# S65-Shield_v12.net
KiCad netlist of a schematic drawn in EAGLE
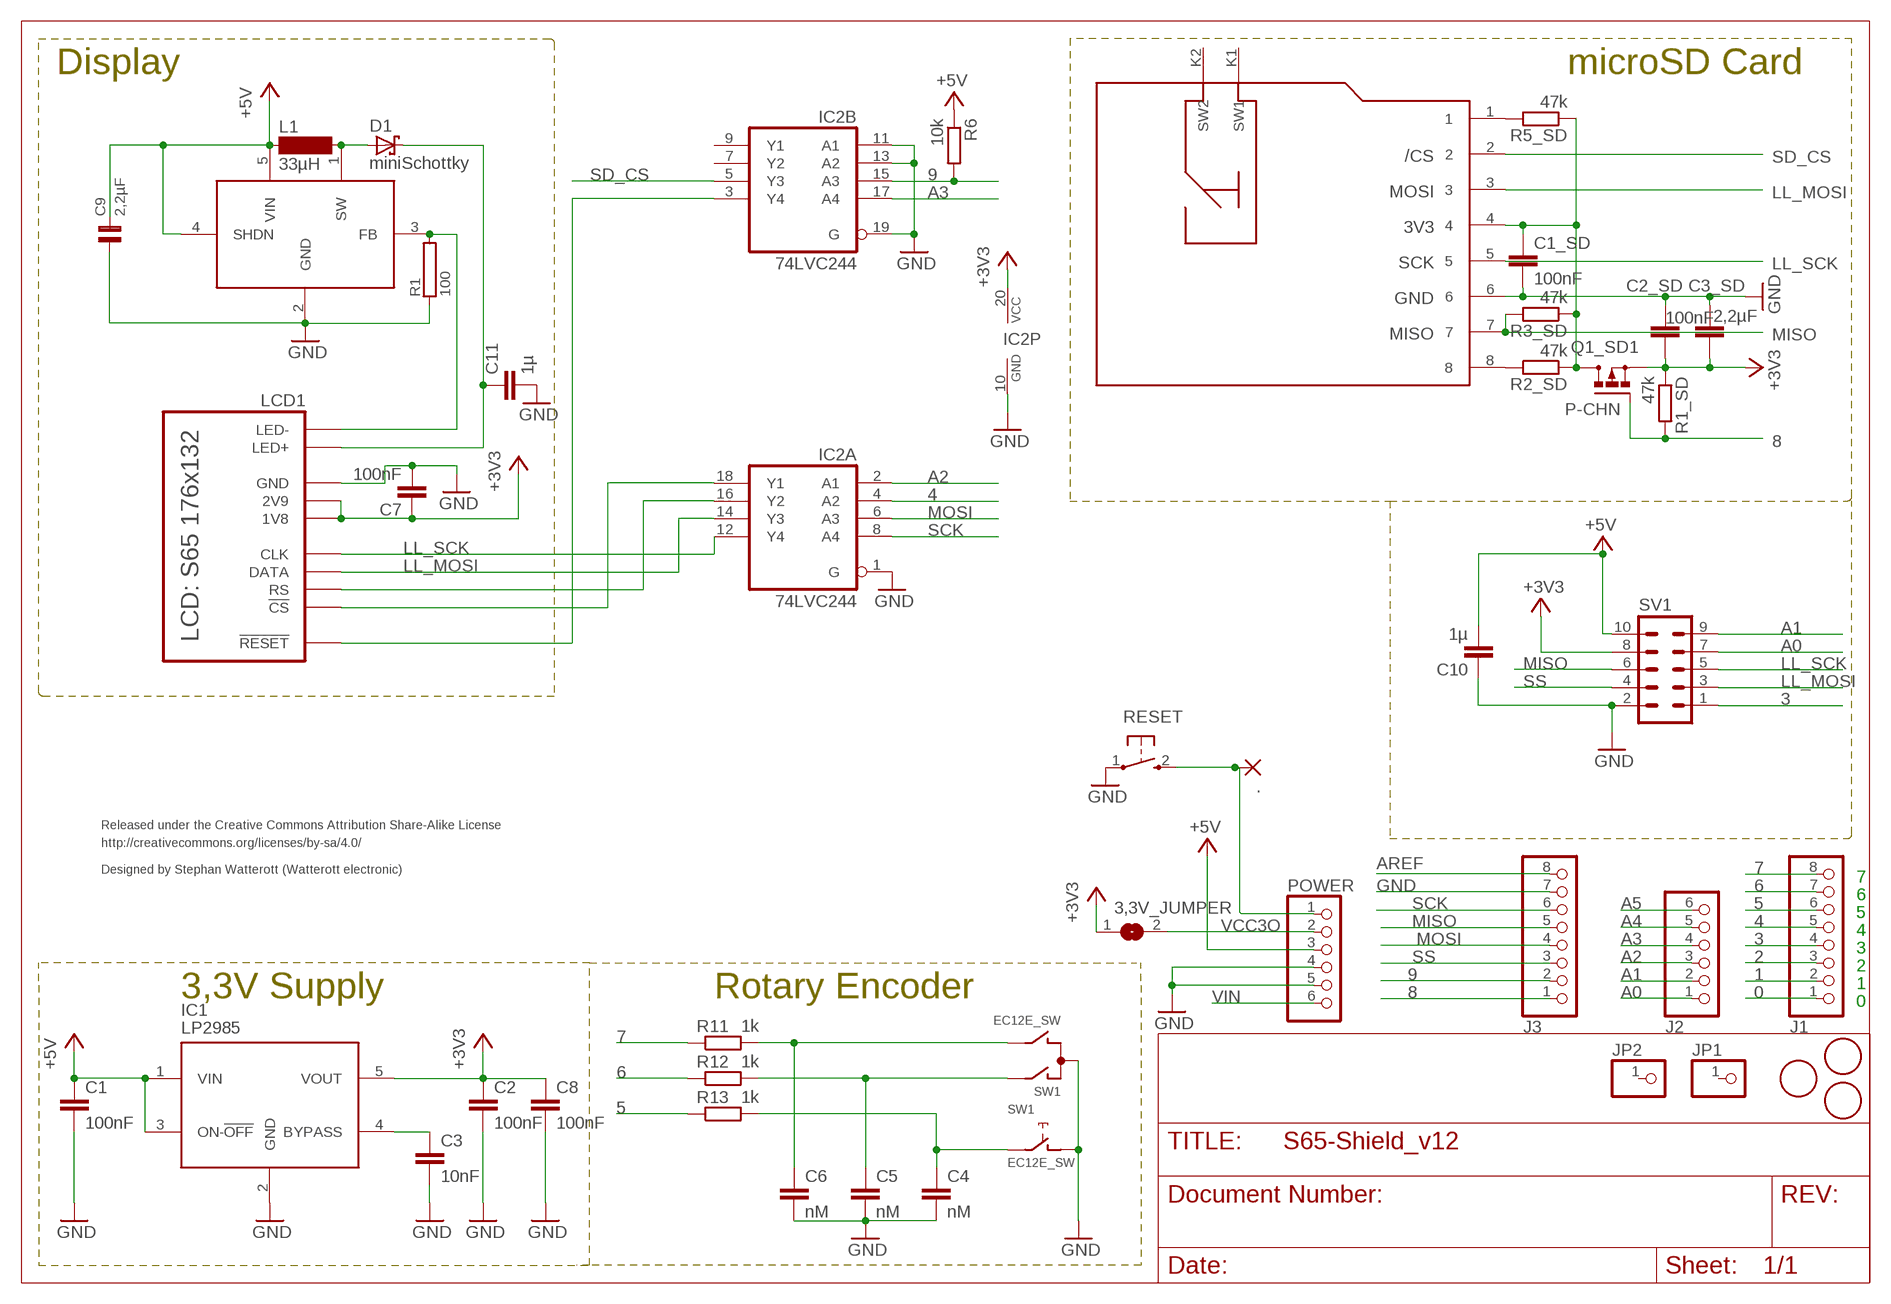
[diagram p0: schematic, sheet 1]

(export (version "E")
  (design (tool "Eeschema 10.0.6"))
  (components
    (comp (ref ".")
      (value "SMD2")
      (footprint "eagle-import:SMD1,27-2,54")
      (libsource (lib "eagle-import") (part "SMD2"))
    )
    (comp (ref "3,3V_JUMPER")
      (value "SJ")
      (footprint "eagle-import:SJ")
      (libsource (lib "eagle-import") (part "SJ"))
    )
    (comp (ref "C1")
      (value "100nF")
      (footprint "eagle-import:C0603")
      (libsource (lib "eagle-import") (part "resistor_C-EUC0603"))
    )
    (comp (ref "C1_SD")
      (value "100nF")
      (footprint "eagle-import:C0603")
      (libsource (lib "eagle-import") (part "C-EUC0603"))
    )
    (comp (ref "C2")
      (value "100nF")
      (footprint "eagle-import:C0603")
      (libsource (lib "eagle-import") (part "resistor_C-EUC0603"))
    )
    (comp (ref "C2_SD")
      (value "100nF")
      (footprint "eagle-import:C0603")
      (libsource (lib "eagle-import") (part "C-EUC0603"))
    )
    (comp (ref "C3")
      (value "10nF")
      (footprint "eagle-import:C0603")
      (libsource (lib "eagle-import") (part "resistor_C-EUC0603"))
    )
    (comp (ref "C3_SD")
      (value "2,2µF")
      (footprint "eagle-import:C0805")
      (libsource (lib "eagle-import") (part "C-EUC0805"))
    )
    (comp (ref "C4")
      (value "nM")
      (footprint "eagle-import:C0603")
      (libsource (lib "eagle-import") (part "resistor_C-EUC0603"))
    )
    (comp (ref "C5")
      (value "nM")
      (footprint "eagle-import:C0603")
      (libsource (lib "eagle-import") (part "resistor_C-EUC0603"))
    )
    (comp (ref "C6")
      (value "nM")
      (footprint "eagle-import:C0603")
      (libsource (lib "eagle-import") (part "resistor_C-EUC0603"))
    )
    (comp (ref "C7")
      (value "100nF")
      (footprint "eagle-import:C0603")
      (libsource (lib "eagle-import") (part "resistor_C-EUC0603"))
    )
    (comp (ref "C8")
      (value "100nF")
      (footprint "eagle-import:C0805")
      (libsource (lib "eagle-import") (part "resistor_C-EUC0805"))
    )
    (comp (ref "C9")
      (value "2,2µF")
      (footprint "eagle-import:0805")
      (libsource (lib "eagle-import") (part "CAP0805"))
    )
    (comp (ref "C10")
      (value "1µ")
      (footprint "eagle-import:C0603")
      (libsource (lib "eagle-import") (part "resistor_C-EUC0603"))
    )
    (comp (ref "C11")
      (value "1µ")
      (footprint "eagle-import:C0603")
      (libsource (lib "eagle-import") (part "resistor_C-EUC0603"))
    )
    (comp (ref "D1")
      (value "miniSchottky")
      (footprint "eagle-import:D0603")
      (libsource (lib "eagle-import") (part "DIODE0603"))
    )
    (comp (ref "IC1")
      (value "LP2985")
      (footprint "eagle-import:SOT23-5")
      (libsource (lib "eagle-import") (part "LP2985"))
    )
    (comp (ref "IC2")
      (value "74LVC244")
      (footprint "eagle-import:SO20W")
      (libsource (lib "eagle-import") (part "74244DWAC"))
    )
    (comp (ref "J1")
      (value "PINHD-1X8")
      (footprint "eagle-import:1X08")
      (libsource (lib "eagle-import") (part "PINHD-1X8"))
    )
    (comp (ref "J2")
      (value "PINHD-1X6")
      (footprint "eagle-import:1X06")
      (libsource (lib "eagle-import") (part "PINHD-1X6"))
    )
    (comp (ref "J3")
      (value "PINHD-1X8")
      (footprint "eagle-import:1X08")
      (libsource (lib "eagle-import") (part "PINHD-1X8"))
    )
    (comp (ref "JP1")
      (value "PINHD-1X1")
      (footprint "eagle-import:1X01")
      (libsource (lib "eagle-import") (part "PINHD-1X1"))
    )
    (comp (ref "JP2")
      (value "PINHD-1X1")
      (footprint "eagle-import:1X01")
      (libsource (lib "eagle-import") (part "PINHD-1X1"))
    )
    (comp (ref "L1")
      (value "33µH")
      (footprint "eagle-import:MS42")
      (libsource (lib "eagle-import") (part "MS42"))
    )
    (comp (ref "LCD1")
      (value "S65")
      (footprint "eagle-import:S65")
      (libsource (lib "eagle-import") (part "S65"))
    )
    (comp (ref "POWER")
      (value "PINHD-1X6")
      (footprint "eagle-import:1X06")
      (libsource (lib "eagle-import") (part "PINHD-1X6"))
    )
    (comp (ref "Q1_SD1")
      (value "P-CHN")
      (footprint "eagle-import:MICRO3")
      (libsource (lib "eagle-import") (part "IRLML6402"))
    )
    (comp (ref "R1")
      (value "100")
      (footprint "eagle-import:0603")
      (libsource (lib "eagle-import") (part "R0603"))
    )
    (comp (ref "R1_SD")
      (value "47k")
      (footprint "eagle-import:R0603")
      (libsource (lib "eagle-import") (part "R-EU_R0603"))
    )
    (comp (ref "R2_SD")
      (value "47k")
      (footprint "eagle-import:R0603")
      (libsource (lib "eagle-import") (part "R-EU_R0603"))
    )
    (comp (ref "R3_SD")
      (value "47k")
      (footprint "eagle-import:R0603")
      (libsource (lib "eagle-import") (part "R-EU_R0603"))
    )
    (comp (ref "R5_SD")
      (value "47k")
      (footprint "eagle-import:R0603")
      (libsource (lib "eagle-import") (part "R-EU_R0603"))
    )
    (comp (ref "R6")
      (value "10k")
      (footprint "eagle-import:R0603")
      (libsource (lib "eagle-import") (part "resistor_R-EU_R0603"))
    )
    (comp (ref "R11")
      (value "1k")
      (footprint "eagle-import:R0603")
      (libsource (lib "eagle-import") (part "resistor_R-EU_R0603"))
    )
    (comp (ref "R12")
      (value "1k")
      (footprint "eagle-import:R0603")
      (libsource (lib "eagle-import") (part "resistor_R-EU_R0603"))
    )
    (comp (ref "R13")
      (value "1k")
      (footprint "eagle-import:R0603")
      (libsource (lib "eagle-import") (part "resistor_R-EU_R0603"))
    )
    (comp (ref "RESET")
      (value "TAST_SMD1")
      (footprint "eagle-import:SMD_TASTER")
      (libsource (lib "eagle-import") (part "TAST_SMD1"))
    )
    (comp (ref "SD")
      (value "MICRO-SD")
      (footprint "eagle-import:MICRO-SD")
      (libsource (lib "eagle-import") (part "MICRO-SD"))
    )
    (comp (ref "SV1")
      (value "ML10")
      (footprint "eagle-import:ML10")
      (libsource (lib "eagle-import") (part "ML10"))
    )
    (comp (ref "SW1")
      (value "EC12E_SW")
      (footprint "eagle-import:ALPS_EC12E_SW")
      (libsource (lib "eagle-import") (part "EC12E_SW"))
    )
    (comp (ref "U$1")
      (value "FIDUCIALMOUNT")
      (footprint "eagle-import:FIDUCIA-MOUNT")
      (libsource (lib "eagle-import") (part "FIDUCIALMOUNT"))
    )
    (comp (ref "U$2")
      (value "FIDUCIALMOUNT")
      (footprint "eagle-import:FIDUCIA-MOUNT")
      (libsource (lib "eagle-import") (part "FIDUCIALMOUNT"))
    )
    (comp (ref "U$3")
      (value "FIDUCIALMOUNT")
      (footprint "eagle-import:FIDUCIA-MOUNT")
      (libsource (lib "eagle-import") (part "FIDUCIALMOUNT"))
    )
    (comp (ref "U$4")
      (value "LM2705")
      (footprint "eagle-import:SOT23-5")
      (libsource (lib "eagle-import") (part "LM2705"))
    )
  )
  (nets
    (net (code "1") (name "+3V3") (class "Default")
      (node (ref "3,3V_JUMPER") (pin "1") (pinfunction "1_1") (pintype "passive"))
      (node (ref "C2") (pin "1") (pinfunction "1_1") (pintype "passive"))
      (node (ref "C2_SD") (pin "2") (pinfunction "2_2") (pintype "passive"))
      (node (ref "C3_SD") (pin "2") (pinfunction "2_2") (pintype "passive"))
      (node (ref "C7") (pin "1") (pinfunction "1_1") (pintype "passive"))
      (node (ref "C8") (pin "1") (pinfunction "1_1") (pintype "passive"))
      (node (ref "IC1") (pin "5") (pinfunction "VOUT_5") (pintype "power_in"))
      (node (ref "IC2") (pin "20") (pinfunction "VCC_20") (pintype "power_in"))
      (node (ref "LCD1") (pin "1V8") (pinfunction "1V8_1V8") (pintype "power_in"))
      (node (ref "LCD1") (pin "2V9") (pinfunction "2V9_2V9") (pintype "power_in"))
      (node (ref "Q1_SD1") (pin "2") (pinfunction "S_2") (pintype "passive"))
      (node (ref "R1_SD") (pin "1") (pinfunction "1_1") (pintype "passive"))
      (node (ref "SV1") (pin "8") (pinfunction "8_8") (pintype "passive"))
    )
    (net (code "2") (name "+5V") (class "Default")
      (node (ref "C1") (pin "1") (pinfunction "1_1") (pintype "passive"))
      (node (ref "C10") (pin "2") (pinfunction "2_2") (pintype "passive"))
      (node (ref "C9") (pin "2") (pinfunction "2_2") (pintype "passive"))
      (node (ref "IC1") (pin "1") (pinfunction "VIN_1") (pintype "power_in"))
      (node (ref "IC1") (pin "3") (pinfunction "ON-~{OFF}_3") (pintype "input"))
      (node (ref "L1") (pin "1") (pinfunction "1_1") (pintype "passive"))
      (node (ref "POWER") (pin "3") (pinfunction "3_3") (pintype "passive"))
      (node (ref "R6") (pin "1") (pinfunction "1_1") (pintype "passive"))
      (node (ref "SV1") (pin "10") (pinfunction "10_10") (pintype "passive"))
      (node (ref "U$4") (pin "4") (pinfunction "SHDN_4") (pintype "bidirectional"))
      (node (ref "U$4") (pin "5") (pinfunction "VIN_5") (pintype "bidirectional"))
    )
    (net (code "3") (name "/0") (class "Default")
      (node (ref "J1") (pin "1") (pinfunction "1_1") (pintype "passive"))
    )
    (net (code "4") (name "/1") (class "Default")
      (node (ref "J1") (pin "2") (pinfunction "2_2") (pintype "passive"))
    )
    (net (code "5") (name "/2") (class "Default")
      (node (ref "J1") (pin "3") (pinfunction "3_3") (pintype "passive"))
    )
    (net (code "6") (name "/3") (class "Default")
      (node (ref "J1") (pin "4") (pinfunction "4_4") (pintype "passive"))
      (node (ref "SV1") (pin "1") (pinfunction "1_1") (pintype "passive"))
    )
    (net (code "7") (name "/4") (class "Default")
      (node (ref "IC2") (pin "4") (pinfunction "A2_4") (pintype "input"))
      (node (ref "J1") (pin "5") (pinfunction "5_5") (pintype "passive"))
    )
    (net (code "8") (name "/5") (class "Default")
      (node (ref "J1") (pin "6") (pinfunction "6_6") (pintype "passive"))
      (node (ref "R13") (pin "1") (pinfunction "1_1") (pintype "passive"))
    )
    (net (code "9") (name "/6") (class "Default")
      (node (ref "J1") (pin "7") (pinfunction "7_7") (pintype "passive"))
      (node (ref "R12") (pin "1") (pinfunction "1_1") (pintype "passive"))
    )
    (net (code "10") (name "/7") (class "Default")
      (node (ref "J1") (pin "8") (pinfunction "8_8") (pintype "passive"))
      (node (ref "R11") (pin "1") (pinfunction "1_1") (pintype "passive"))
    )
    (net (code "11") (name "/8") (class "Default")
      (node (ref "J3") (pin "1") (pinfunction "1_1") (pintype "passive"))
      (node (ref "Q1_SD1") (pin "1") (pinfunction "G_1") (pintype "passive"))
      (node (ref "R1_SD") (pin "2") (pinfunction "2_2") (pintype "passive"))
    )
    (net (code "12") (name "/9") (class "Default")
      (node (ref "IC2") (pin "15") (pinfunction "A3_15") (pintype "input"))
      (node (ref "J3") (pin "2") (pinfunction "2_2") (pintype "passive"))
      (node (ref "R6") (pin "2") (pinfunction "2_2") (pintype "passive"))
    )
    (net (code "13") (name "/A0") (class "Default")
      (node (ref "J2") (pin "1") (pinfunction "1_1") (pintype "passive"))
      (node (ref "SV1") (pin "7") (pinfunction "7_7") (pintype "passive"))
    )
    (net (code "14") (name "/A1") (class "Default")
      (node (ref "J2") (pin "2") (pinfunction "2_2") (pintype "passive"))
      (node (ref "SV1") (pin "9") (pinfunction "9_9") (pintype "passive"))
    )
    (net (code "15") (name "/A2") (class "Default")
      (node (ref "IC2") (pin "2") (pinfunction "A1_2") (pintype "input"))
      (node (ref "J2") (pin "3") (pinfunction "3_3") (pintype "passive"))
    )
    (net (code "16") (name "/A3") (class "Default")
      (node (ref "IC2") (pin "17") (pinfunction "A4_17") (pintype "input"))
      (node (ref "J2") (pin "4") (pinfunction "4_4") (pintype "passive"))
    )
    (net (code "17") (name "/A4") (class "Default")
      (node (ref "J2") (pin "5") (pinfunction "5_5") (pintype "passive"))
    )
    (net (code "18") (name "/A5") (class "Default")
      (node (ref "J2") (pin "6") (pinfunction "6_6") (pintype "passive"))
    )
    (net (code "19") (name "/AREF") (class "Default")
      (node (ref "J3") (pin "8") (pinfunction "8_8") (pintype "passive"))
    )
    (net (code "20") (name "/LL_MOSI") (class "Default")
      (node (ref "IC2") (pin "14") (pinfunction "Y3_14") (pintype "tri_state"))
      (node (ref "LCD1") (pin "DATA") (pinfunction "DATA_DATA") (pintype "bidirectional"))
      (node (ref "SD") (pin "3") (pinfunction "3_3") (pintype "bidirectional"))
      (node (ref "SV1") (pin "3") (pinfunction "3_3") (pintype "passive"))
    )
    (net (code "21") (name "/LL_SCK") (class "Default")
      (node (ref "IC2") (pin "12") (pinfunction "Y4_12") (pintype "tri_state"))
      (node (ref "LCD1") (pin "CLK") (pinfunction "CLK_CLK") (pintype "bidirectional"))
      (node (ref "SD") (pin "5") (pinfunction "5_5") (pintype "bidirectional"))
      (node (ref "SV1") (pin "5") (pinfunction "5_5") (pintype "passive"))
    )
    (net (code "22") (name "/MISO") (class "Default")
      (node (ref "J3") (pin "5") (pinfunction "5_5") (pintype "passive"))
      (node (ref "R3_SD") (pin "2") (pinfunction "2_2") (pintype "passive"))
      (node (ref "SD") (pin "7") (pinfunction "7_7") (pintype "bidirectional"))
      (node (ref "SV1") (pin "6") (pinfunction "6_6") (pintype "passive"))
    )
    (net (code "23") (name "/MOSI") (class "Default")
      (node (ref "IC2") (pin "6") (pinfunction "A3_6") (pintype "input"))
      (node (ref "J3") (pin "4") (pinfunction "4_4") (pintype "passive"))
    )
    (net (code "24") (name "/SCK") (class "Default")
      (node (ref "IC2") (pin "8") (pinfunction "A4_8") (pintype "input"))
      (node (ref "J3") (pin "6") (pinfunction "6_6") (pintype "passive"))
    )
    (net (code "25") (name "/SD_CS") (class "Default")
      (node (ref "IC2") (pin "5") (pinfunction "Y3_5") (pintype "tri_state"))
      (node (ref "SD") (pin "2") (pinfunction "2_2") (pintype "bidirectional"))
    )
    (net (code "26") (name "/SS") (class "Default")
      (node (ref "J3") (pin "3") (pinfunction "3_3") (pintype "passive"))
      (node (ref "SV1") (pin "4") (pinfunction "4_4") (pintype "passive"))
    )
    (net (code "27") (name "/VCC3O") (class "Default")
      (node (ref "3,3V_JUMPER") (pin "2") (pinfunction "2_2") (pintype "passive"))
      (node (ref "POWER") (pin "2") (pinfunction "2_2") (pintype "passive"))
    )
    (net (code "28") (name "/VIN") (class "Default")
      (node (ref "POWER") (pin "6") (pinfunction "6_6") (pintype "passive"))
    )
    (net (code "29") (name "GND") (class "Default")
      (node (ref "C1") (pin "2") (pinfunction "2_2") (pintype "passive"))
      (node (ref "C10") (pin "1") (pinfunction "1_1") (pintype "passive"))
      (node (ref "C11") (pin "2") (pinfunction "2_2") (pintype "passive"))
      (node (ref "C1_SD") (pin "2") (pinfunction "2_2") (pintype "passive"))
      (node (ref "C2") (pin "2") (pinfunction "2_2") (pintype "passive"))
      (node (ref "C2_SD") (pin "1") (pinfunction "1_1") (pintype "passive"))
      (node (ref "C3") (pin "2") (pinfunction "2_2") (pintype "passive"))
      (node (ref "C3_SD") (pin "1") (pinfunction "1_1") (pintype "passive"))
      (node (ref "C4") (pin "2") (pinfunction "2_2") (pintype "passive"))
      (node (ref "C5") (pin "2") (pinfunction "2_2") (pintype "passive"))
      (node (ref "C6") (pin "2") (pinfunction "2_2") (pintype "passive"))
      (node (ref "C7") (pin "2") (pinfunction "2_2") (pintype "passive"))
      (node (ref "C8") (pin "2") (pinfunction "2_2") (pintype "passive"))
      (node (ref "C9") (pin "1") (pinfunction "1_1") (pintype "passive"))
      (node (ref "IC1") (pin "2") (pinfunction "GND_2") (pintype "power_in"))
      (node (ref "IC2") (pin "1") (pinfunction "G_1") (pintype "input"))
      (node (ref "IC2") (pin "10") (pinfunction "GND_10") (pintype "power_in"))
      (node (ref "IC2") (pin "11") (pinfunction "A1_11") (pintype "input"))
      (node (ref "IC2") (pin "13") (pinfunction "A2_13") (pintype "input"))
      (node (ref "IC2") (pin "19") (pinfunction "G_19") (pintype "input"))
      (node (ref "J3") (pin "7") (pinfunction "7_7") (pintype "passive"))
      (node (ref "LCD1") (pin "GND") (pinfunction "GND_GND") (pintype "power_in"))
      (node (ref "POWER") (pin "4") (pinfunction "4_4") (pintype "passive"))
      (node (ref "POWER") (pin "5") (pinfunction "5_5") (pintype "passive"))
      (node (ref "R1") (pin "1") (pinfunction "1_1") (pintype "passive"))
      (node (ref "RESET") (pin "1") (pinfunction "P_1") (pintype "passive"))
      (node (ref "SD") (pin "6") (pinfunction "6_6") (pintype "bidirectional"))
      (node (ref "SV1") (pin "2") (pinfunction "2_2") (pintype "passive"))
      (node (ref "SW1") (pin "C") (pinfunction "C_C") (pintype "passive"))
      (node (ref "SW1") (pin "D") (pinfunction "1_D") (pintype "passive"))
      (node (ref "U$4") (pin "2") (pinfunction "GND_2") (pintype "bidirectional"))
    )
    (net (code "30") (name "Net-(.-P)") (class "Default")
      (node (ref ".") (pin "1") (pinfunction "P_1") (pintype "passive"))
      (node (ref "POWER") (pin "1") (pinfunction "1_1") (pintype "passive"))
      (node (ref "RESET") (pin "2") (pinfunction "S_2") (pintype "passive"))
    )
    (net (code "31") (name "Net-(C5-Pad1)") (class "Default")
      (node (ref "C5") (pin "1") (pinfunction "1_1") (pintype "passive"))
      (node (ref "R12") (pin "2") (pinfunction "2_2") (pintype "passive"))
      (node (ref "SW1") (pin "A") (pinfunction "A_A") (pintype "passive"))
    )
    (net (code "32") (name "Net-(C6-Pad1)") (class "Default")
      (node (ref "C6") (pin "1") (pinfunction "1_1") (pintype "passive"))
      (node (ref "R11") (pin "2") (pinfunction "2_2") (pintype "passive"))
      (node (ref "SW1") (pin "B") (pinfunction "B_B") (pintype "passive"))
    )
    (net (code "33") (name "Net-(D1-A)") (class "Default")
      (node (ref "D1") (pin "2") (pinfunction "A_2") (pintype "passive"))
      (node (ref "L1") (pin "2") (pinfunction "2_2") (pintype "passive"))
      (node (ref "U$4") (pin "1") (pinfunction "SW_1") (pintype "bidirectional"))
    )
    (net (code "34") (name "Net-(D1-C)") (class "Default")
      (node (ref "C11") (pin "1") (pinfunction "1_1") (pintype "passive"))
      (node (ref "D1") (pin "1") (pinfunction "C_1") (pintype "passive"))
      (node (ref "LCD1") (pin "LED+") (pinfunction "LED+_LED+") (pintype "power_in"))
    )
    (net (code "35") (name "Net-(IC1-BYPASS)") (class "Default")
      (node (ref "C3") (pin "1") (pinfunction "1_1") (pintype "passive"))
      (node (ref "IC1") (pin "4") (pinfunction "BYPASS_4") (pintype "input"))
    )
    (net (code "36") (name "Net-(IC2A-Y1)") (class "Default")
      (node (ref "IC2") (pin "18") (pinfunction "Y1_18") (pintype "tri_state"))
      (node (ref "LCD1") (pin "CS") (pinfunction "~{CS}_CS") (pintype "bidirectional"))
    )
    (net (code "37") (name "Net-(IC2A-Y2)") (class "Default")
      (node (ref "IC2") (pin "16") (pinfunction "Y2_16") (pintype "tri_state"))
      (node (ref "LCD1") (pin "RS") (pinfunction "RS_RS") (pintype "bidirectional"))
    )
    (net (code "38") (name "Net-(IC2B-Y4)") (class "Default")
      (node (ref "IC2") (pin "3") (pinfunction "Y4_3") (pintype "tri_state"))
      (node (ref "LCD1") (pin "RESET") (pinfunction "~{RESET}_RESET") (pintype "bidirectional"))
    )
    (net (code "39") (name "Net-(Q1_SD1-D)") (class "Default")
      (node (ref "C1_SD") (pin "1") (pinfunction "1_1") (pintype "passive"))
      (node (ref "Q1_SD1") (pin "3") (pinfunction "D_3") (pintype "passive"))
      (node (ref "R2_SD") (pin "1") (pinfunction "1_1") (pintype "passive"))
      (node (ref "R3_SD") (pin "1") (pinfunction "1_1") (pintype "passive"))
      (node (ref "R5_SD") (pin "1") (pinfunction "1_1") (pintype "passive"))
      (node (ref "SD") (pin "4") (pinfunction "4_4") (pintype "bidirectional"))
    )
    (net (code "40") (name "Net-(R2_SD-Pad2)") (class "Default")
      (node (ref "R2_SD") (pin "2") (pinfunction "2_2") (pintype "passive"))
      (node (ref "SD") (pin "8") (pinfunction "8_8") (pintype "bidirectional"))
    )
    (net (code "41") (name "Net-(R5_SD-Pad2)") (class "Default")
      (node (ref "R5_SD") (pin "2") (pinfunction "2_2") (pintype "passive"))
      (node (ref "SD") (pin "1") (pinfunction "1_1") (pintype "bidirectional"))
    )
    (net (code "42") (name "Net-(SW1B-2)") (class "Default")
      (node (ref "C4") (pin "1") (pinfunction "1_1") (pintype "passive"))
      (node (ref "R13") (pin "2") (pinfunction "2_2") (pintype "passive"))
      (node (ref "SW1") (pin "E") (pinfunction "2_E") (pintype "passive"))
    )
    (net (code "43") (name "Net-(U$4-FB)") (class "Default")
      (node (ref "LCD1") (pin "LED-") (pinfunction "LED-_LED-") (pintype "power_in"))
      (node (ref "R1") (pin "2") (pinfunction "2_2") (pintype "passive"))
      (node (ref "U$4") (pin "3") (pinfunction "FB_3") (pintype "bidirectional"))
    )
    (net (code "44") (name "unconnected-(IC2B-Y1-Pad9)") (class "Default")
      (node (ref "IC2") (pin "9") (pinfunction "Y1_9") (pintype "tri_state"))
    )
    (net (code "45") (name "unconnected-(IC2B-Y2-Pad7)") (class "Default")
      (node (ref "IC2") (pin "7") (pinfunction "Y2_7") (pintype "tri_state"))
    )
    (net (code "46") (name "unconnected-(JP1-Pad1)") (class "Default")
      (node (ref "JP1") (pin "1") (pinfunction "1_1") (pintype "passive"))
    )
    (net (code "47") (name "unconnected-(JP2-Pad1)") (class "Default")
      (node (ref "JP2") (pin "1") (pinfunction "1_1") (pintype "passive"))
    )
    (net (code "48") (name "unconnected-(SD-SW1-PadK1)") (class "Default")
      (node (ref "SD") (pin "K1") (pinfunction "SW1_K1") (pintype "bidirectional"))
    )
    (net (code "49") (name "unconnected-(SD-SW2-PadK2)") (class "Default")
      (node (ref "SD") (pin "K2") (pinfunction "SW2_K2") (pintype "bidirectional"))
    )
  )
)
